# Expand_v1_02.net
KiCad netlist of a schematic drawn in EAGLE
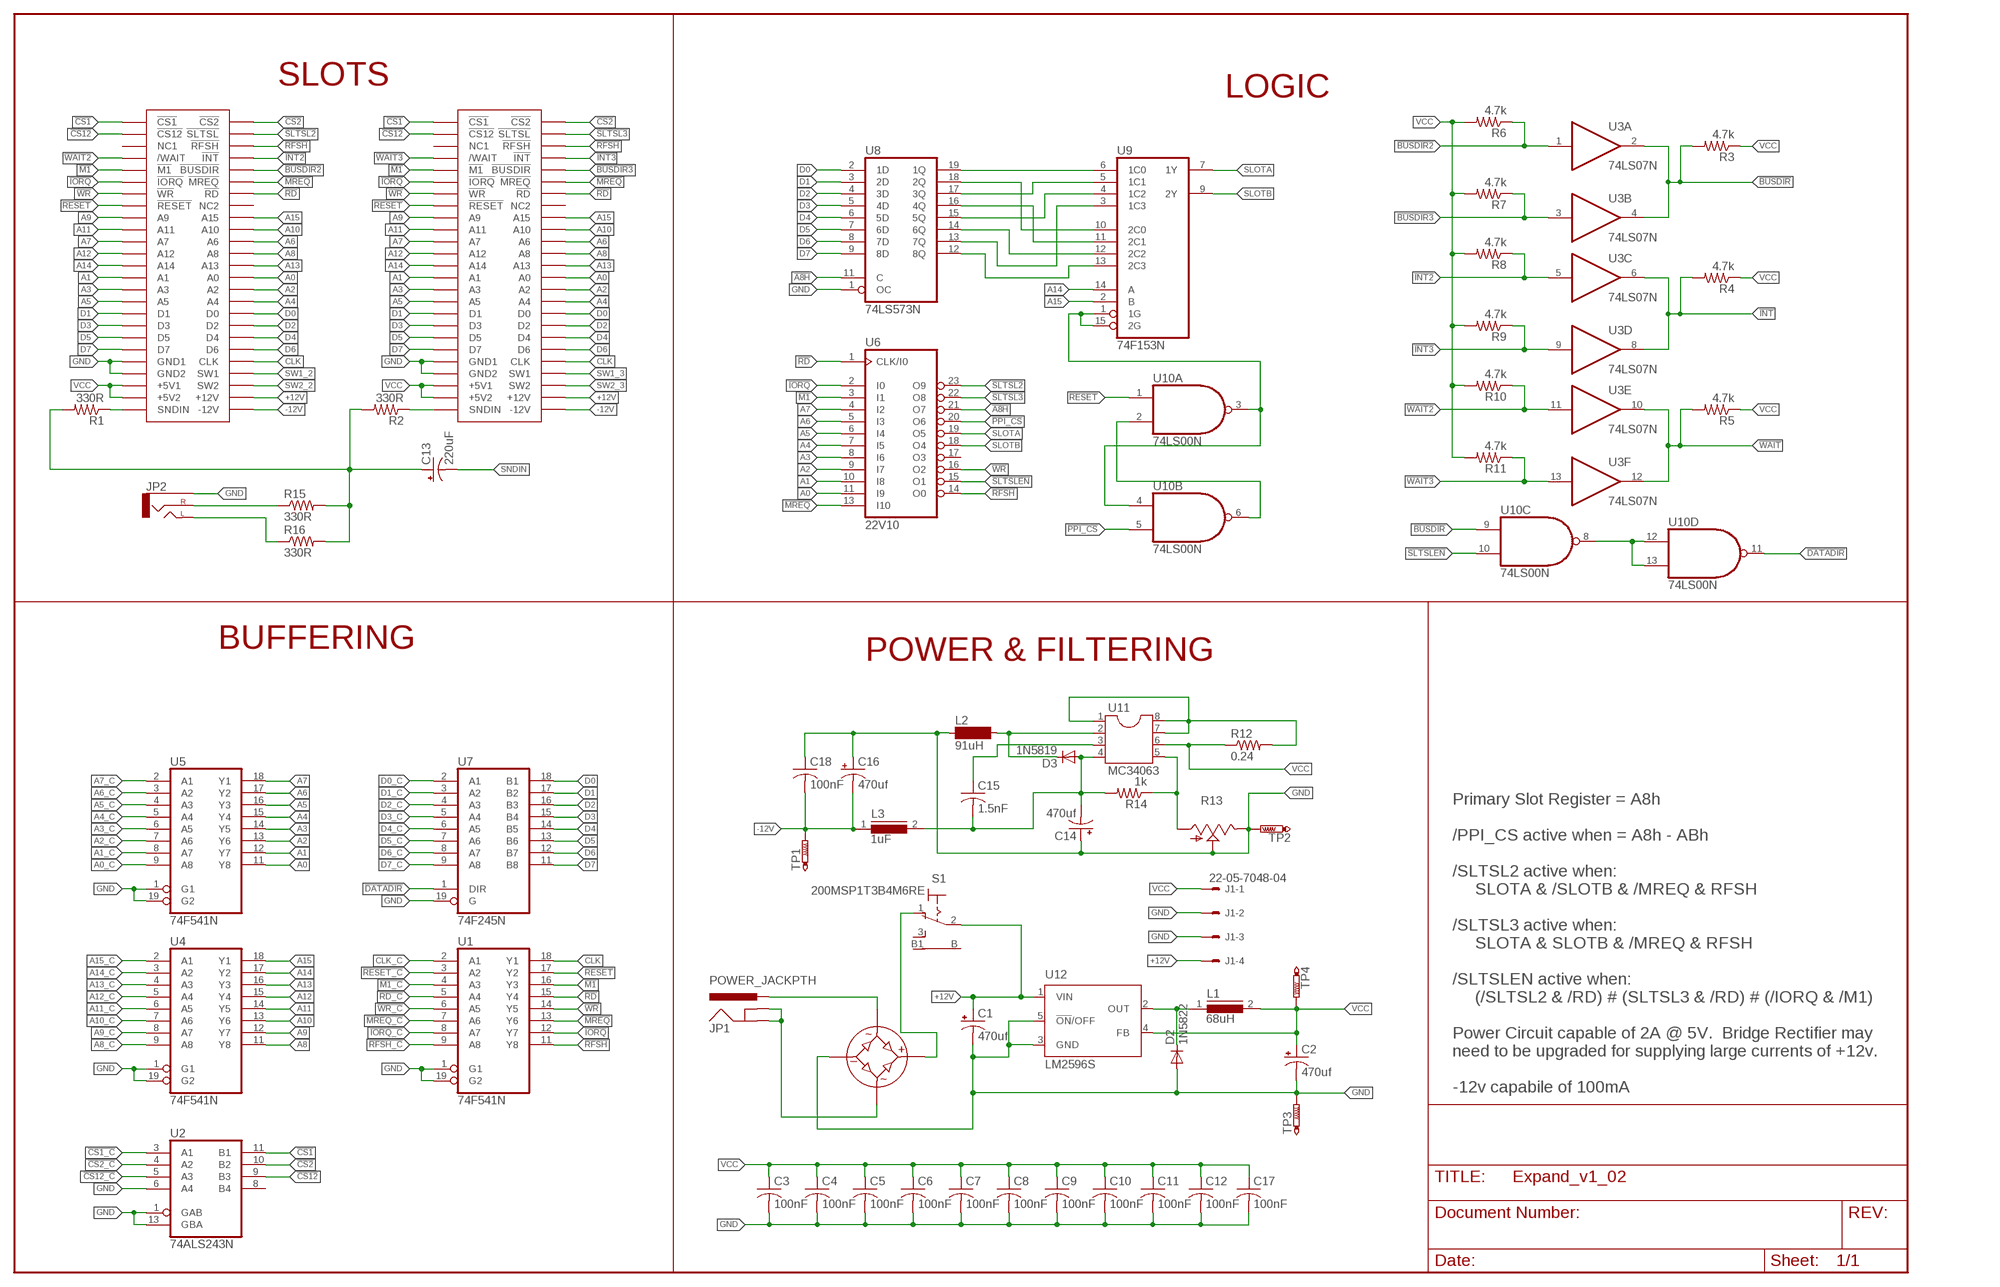
[diagram p0: schematic, sheet 1]

(export (version "E")
  (design (tool "Eeschema 10.0.6"))
  (components
    (comp (ref "C1")
      (value "470uf")
      (footprint "eagle-import:E5-10,5")
      (libsource (lib "eagle-import") (part "CPOL-USE5-10.5"))
    )
    (comp (ref "C2")
      (value "470uf")
      (footprint "eagle-import:E5-10,5")
      (libsource (lib "eagle-import") (part "CPOL-USE5-10.5"))
    )
    (comp (ref "C3")
      (value "100nF")
      (footprint "eagle-import:C050-030X075")
      (libsource (lib "eagle-import") (part "C-US050-030X075"))
    )
    (comp (ref "C4")
      (value "100nF")
      (footprint "eagle-import:C050-030X075")
      (libsource (lib "eagle-import") (part "C-US050-030X075"))
    )
    (comp (ref "C5")
      (value "100nF")
      (footprint "eagle-import:C050-030X075")
      (libsource (lib "eagle-import") (part "C-US050-030X075"))
    )
    (comp (ref "C6")
      (value "100nF")
      (footprint "eagle-import:C050-030X075")
      (libsource (lib "eagle-import") (part "C-US050-030X075"))
    )
    (comp (ref "C7")
      (value "100nF")
      (footprint "eagle-import:C050-030X075")
      (libsource (lib "eagle-import") (part "C-US050-030X075"))
    )
    (comp (ref "C8")
      (value "100nF")
      (footprint "eagle-import:C050-030X075")
      (libsource (lib "eagle-import") (part "C-US050-030X075"))
    )
    (comp (ref "C9")
      (value "100nF")
      (footprint "eagle-import:C050-030X075")
      (libsource (lib "eagle-import") (part "C-US050-030X075"))
    )
    (comp (ref "C10")
      (value "100nF")
      (footprint "eagle-import:C050-030X075")
      (libsource (lib "eagle-import") (part "C-US050-030X075"))
    )
    (comp (ref "C11")
      (value "100nF")
      (footprint "eagle-import:C050-030X075")
      (libsource (lib "eagle-import") (part "C-US050-030X075"))
    )
    (comp (ref "C12")
      (value "100nF")
      (footprint "eagle-import:C050-030X075")
      (libsource (lib "eagle-import") (part "C-US050-030X075"))
    )
    (comp (ref "C13")
      (value "220uF")
      (footprint "eagle-import:E2-4")
      (libsource (lib "eagle-import") (part "CPOL-USE2-4"))
    )
    (comp (ref "C14")
      (value "470uf")
      (footprint "eagle-import:E5-10,5")
      (libsource (lib "eagle-import") (part "CPOL-USE5-10.5"))
    )
    (comp (ref "C15")
      (value "1.5nF")
      (footprint "eagle-import:C050-030X075")
      (libsource (lib "eagle-import") (part "C-US050-030X075"))
    )
    (comp (ref "C16")
      (value "470uf")
      (footprint "eagle-import:E5-10,5")
      (libsource (lib "eagle-import") (part "CPOL-USE5-10.5"))
    )
    (comp (ref "C17")
      (value "100nF")
      (footprint "eagle-import:C050-030X075")
      (libsource (lib "eagle-import") (part "C-US050-030X075"))
    )
    (comp (ref "C18")
      (value "100nF")
      (footprint "eagle-import:C050-030X075")
      (libsource (lib "eagle-import") (part "C-US050-030X075"))
    )
    (comp (ref "CONN2")
      (value "MSX_CART_SLOT")
      (footprint "eagle-import:CART_SLOT")
      (libsource (lib "eagle-import") (part "MSX_CART_SLOT"))
    )
    (comp (ref "CONN3")
      (value "MSX_CART_SLOT")
      (footprint "eagle-import:CART_SLOT")
      (libsource (lib "eagle-import") (part "MSX_CART_SLOT"))
    )
    (comp (ref "D1")
      (value "2W10")
      (footprint "eagle-import:2W10")
      (libsource (lib "eagle-import") (part "2W10"))
    )
    (comp (ref "D2")
      (value "1N5822")
      (footprint "eagle-import:DO201-15")
      (libsource (lib "eagle-import") (part "1N5624"))
    )
    (comp (ref "D3")
      (value "1N5819")
      (footprint "eagle-import:DO15-12")
      (libsource (lib "eagle-import") (part "DIODE-DO15-12"))
    )
    (comp (ref "J1")
      (value "22-05-7048-04")
      (footprint "eagle-import:7395-04")
      (libsource (lib "eagle-import") (part "22-?-0405-7048"))
    )
    (comp (ref "JP1")
      (value "POWER_JACKPTH")
      (footprint "eagle-import:POWER_JACK_PTH")
      (libsource (lib "eagle-import") (part "POWER_JACKPTH"))
    )
    (comp (ref "JP2")
      (value "AUDIO-JACK1:1")
      (footprint "eagle-import:STEREOJACK2.5MM")
      (libsource (lib "eagle-import") (part "AUDIO-JACK1{colon}1"))
    )
    (comp (ref "L1")
      (value "68uH")
      (footprint "eagle-import:A26GFC")
      (libsource (lib "eagle-import") (part "A26GFC"))
    )
    (comp (ref "L2")
      (value "91uH")
      (footprint "eagle-import:BS11")
      (libsource (lib "eagle-import") (part "BS11"))
    )
    (comp (ref "L3")
      (value "1uF")
      (footprint "eagle-import:MCC10")
      (libsource (lib "eagle-import") (part "MCC10"))
    )
    (comp (ref "R1")
      (value "330R")
      (footprint "eagle-import:0207_7")
      (libsource (lib "eagle-import") (part "R-US_0207/7"))
    )
    (comp (ref "R2")
      (value "330R")
      (footprint "eagle-import:0207_7")
      (libsource (lib "eagle-import") (part "R-US_0207/7"))
    )
    (comp (ref "R3")
      (value "4.7k")
      (footprint "eagle-import:0207_7")
      (libsource (lib "eagle-import") (part "R-US_0207/7"))
    )
    (comp (ref "R4")
      (value "4.7k")
      (footprint "eagle-import:0207_7")
      (libsource (lib "eagle-import") (part "R-US_0207/7"))
    )
    (comp (ref "R5")
      (value "4.7k")
      (footprint "eagle-import:0207_7")
      (libsource (lib "eagle-import") (part "R-US_0207/7"))
    )
    (comp (ref "R6")
      (value "4.7k")
      (footprint "eagle-import:0207_7")
      (libsource (lib "eagle-import") (part "R-US_0207/7"))
    )
    (comp (ref "R7")
      (value "4.7k")
      (footprint "eagle-import:0207_7")
      (libsource (lib "eagle-import") (part "R-US_0207/7"))
    )
    (comp (ref "R8")
      (value "4.7k")
      (footprint "eagle-import:0207_7")
      (libsource (lib "eagle-import") (part "R-US_0207/7"))
    )
    (comp (ref "R9")
      (value "4.7k")
      (footprint "eagle-import:0207_7")
      (libsource (lib "eagle-import") (part "R-US_0207/7"))
    )
    (comp (ref "R10")
      (value "4.7k")
      (footprint "eagle-import:0207_7")
      (libsource (lib "eagle-import") (part "R-US_0207/7"))
    )
    (comp (ref "R11")
      (value "4.7k")
      (footprint "eagle-import:0207_7")
      (libsource (lib "eagle-import") (part "R-US_0207/7"))
    )
    (comp (ref "R12")
      (value "0.24")
      (footprint "eagle-import:0207_10")
      (libsource (lib "eagle-import") (part "R-US_0207/10"))
    )
    (comp (ref "R13")
      (value "TRIM_US-RJ9W")
      (footprint "eagle-import:RJ9W")
      (libsource (lib "eagle-import") (part "TRIM_US-RJ9W"))
    )
    (comp (ref "R14")
      (value "1k")
      (footprint "eagle-import:0207_7")
      (libsource (lib "eagle-import") (part "R-US_0207/7"))
    )
    (comp (ref "R15")
      (value "330R")
      (footprint "eagle-import:0207_7")
      (libsource (lib "eagle-import") (part "R-US_0207/7"))
    )
    (comp (ref "R16")
      (value "330R")
      (footprint "eagle-import:0207_7")
      (libsource (lib "eagle-import") (part "R-US_0207/7"))
    )
    (comp (ref "S1")
      (value "200MSP1T3B4M6RE")
      (footprint "eagle-import:9070-1W")
      (libsource (lib "eagle-import") (part "9070-1W"))
    )
    (comp (ref "TP1")
      (value "PTR1B2,54")
      (footprint "eagle-import:B2,54")
      (libsource (lib "eagle-import") (part "PTR1B2,54"))
    )
    (comp (ref "TP2")
      (value "PTR1B2,54")
      (footprint "eagle-import:B2,54")
      (libsource (lib "eagle-import") (part "PTR1B2,54"))
    )
    (comp (ref "TP3")
      (value "PTR1B2,54")
      (footprint "eagle-import:B2,54")
      (libsource (lib "eagle-import") (part "PTR1B2,54"))
    )
    (comp (ref "TP4")
      (value "PTR1B2,54")
      (footprint "eagle-import:B2,54")
      (libsource (lib "eagle-import") (part "PTR1B2,54"))
    )
    (comp (ref "U1")
      (value "74F541N")
      (footprint "eagle-import:DIL20")
      (libsource (lib "eagle-import") (part "74541NLS"))
    )
    (comp (ref "U2")
      (value "74ALS243N")
      (footprint "eagle-import:DIL14")
      (libsource (lib "eagle-import") (part "74243NLS"))
    )
    (comp (ref "U3")
      (value "74LS07N")
      (footprint "eagle-import:DIL14")
      (libsource (lib "eagle-import") (part "7407N"))
    )
    (comp (ref "U4")
      (value "74F541N")
      (footprint "eagle-import:DIL20")
      (libsource (lib "eagle-import") (part "74541NLS"))
    )
    (comp (ref "U5")
      (value "74F541N")
      (footprint "eagle-import:DIL20")
      (libsource (lib "eagle-import") (part "74541NLS"))
    )
    (comp (ref "U6")
      (value "22V10")
      (footprint "eagle-import:DIL24-3")
      (fields (field (name "MPN") "GAL22V10D-7LPN"))
      (libsource (lib "eagle-import") (part "22V10"))
    )
    (comp (ref "U7")
      (value "74F245N")
      (footprint "eagle-import:DIL20")
      (libsource (lib "eagle-import") (part "74245NLS"))
    )
    (comp (ref "U8")
      (value "74LS573N")
      (footprint "eagle-import:DIL20")
      (libsource (lib "eagle-import") (part "74573NAS"))
    )
    (comp (ref "U9")
      (value "74F153N")
      (footprint "eagle-import:DIL16")
      (libsource (lib "eagle-import") (part "74153NS"))
    )
    (comp (ref "U10")
      (value "74LS00N")
      (footprint "eagle-import:DIL14")
      (libsource (lib "eagle-import") (part "7400N"))
    )
    (comp (ref "U11")
      (value "MC34063")
      (footprint "eagle-import:DIL08")
      (libsource (lib "eagle-import") (part "DIL8"))
    )
    (comp (ref "U12")
      (value "LM2596S")
      (footprint "eagle-import:TO263-5")
      (fields (field (name "MF") "NATIONAL SEMICONDUCTOR") (field (name "MPN") "LM2596S-ADJ/NOPB"))
      (libsource (lib "eagle-import") (part "LM2596S"))
    )
  )
  (nets
    (net (code "1") (name "+12V") (class "Default")
      (node (ref "C1") (pin "+") (pinfunction "+_+") (pintype "passive"))
      (node (ref "CONN2") (pin "P$48") (pinfunction "+12V_P$48") (pintype "bidirectional"))
      (node (ref "CONN3") (pin "P$48") (pinfunction "+12V_P$48") (pintype "bidirectional"))
      (node (ref "J1") (pin "4") (pinfunction "S_4") (pintype "passive"))
      (node (ref "S1") (pin "2") (pinfunction "P_2") (pintype "passive"))
      (node (ref "U12") (pin "1") (pinfunction "VIN_1") (pintype "input"))
    )
    (net (code "2") (name "-12V") (class "Default")
      (node (ref "C16") (pin "-") (pinfunction "-_-") (pintype "passive"))
      (node (ref "C18") (pin "2") (pinfunction "2_2") (pintype "passive"))
      (node (ref "CONN2") (pin "P$50") (pinfunction "-12V_P$50") (pintype "bidirectional"))
      (node (ref "CONN3") (pin "P$50") (pinfunction "-12V_P$50") (pintype "bidirectional"))
      (node (ref "L3") (pin "1") (pinfunction "1_1") (pintype "passive"))
      (node (ref "TP1") (pin "TP") (pinfunction "TP_TP") (pintype "input"))
    )
    (net (code "3") (name "/~{A8H}") (class "Default")
      (node (ref "U6") (pin "21") (pinfunction "O7_21") (pintype "bidirectional"))
      (node (ref "U8") (pin "11") (pinfunction "C_11") (pintype "input"))
    )
    (net (code "4") (name "/~{BUSDIR2}") (class "Default")
      (node (ref "CONN2") (pin "P$10") (pinfunction "~{BUSDIR}_P$10") (pintype "bidirectional"))
      (node (ref "R6") (pin "1") (pinfunction "1_1") (pintype "passive"))
      (node (ref "U3") (pin "1") (pinfunction "I_1") (pintype "input"))
    )
    (net (code "5") (name "/~{BUSDIR3}") (class "Default")
      (node (ref "CONN3") (pin "P$10") (pinfunction "~{BUSDIR}_P$10") (pintype "bidirectional"))
      (node (ref "R7") (pin "1") (pinfunction "1_1") (pintype "passive"))
      (node (ref "U3") (pin "3") (pinfunction "I_3") (pintype "input"))
    )
    (net (code "6") (name "/~{BUSDIR}") (class "Default")
      (node (ref "R3") (pin "2") (pinfunction "2_2") (pintype "passive"))
      (node (ref "U10") (pin "9") (pinfunction "I0_9") (pintype "input"))
      (node (ref "U3") (pin "2") (pinfunction "O_2") (pintype "open_collector"))
      (node (ref "U3") (pin "4") (pinfunction "O_4") (pintype "open_collector"))
    )
    (net (code "7") (name "/~{CS1_C}") (class "Default")
      (node (ref "U2") (pin "3") (pinfunction "A1_3") (pintype "bidirectional"))
    )
    (net (code "8") (name "/~{CS1}") (class "Default")
      (node (ref "CONN2") (pin "P$1") (pinfunction "~{CS1}_P$1") (pintype "bidirectional"))
      (node (ref "CONN3") (pin "P$1") (pinfunction "~{CS1}_P$1") (pintype "bidirectional"))
      (node (ref "U2") (pin "11") (pinfunction "B1_11") (pintype "bidirectional"))
    )
    (net (code "9") (name "/~{CS2_C}") (class "Default")
      (node (ref "U2") (pin "4") (pinfunction "A2_4") (pintype "bidirectional"))
    )
    (net (code "10") (name "/~{CS2}") (class "Default")
      (node (ref "CONN2") (pin "P$2") (pinfunction "~{CS2}_P$2") (pintype "bidirectional"))
      (node (ref "CONN3") (pin "P$2") (pinfunction "~{CS2}_P$2") (pintype "bidirectional"))
      (node (ref "U2") (pin "10") (pinfunction "B2_10") (pintype "bidirectional"))
    )
    (net (code "11") (name "/~{CS12_C}") (class "Default")
      (node (ref "U2") (pin "5") (pinfunction "A3_5") (pintype "bidirectional"))
    )
    (net (code "12") (name "/~{CS12}") (class "Default")
      (node (ref "CONN2") (pin "P$3") (pinfunction "~{CS12}_P$3") (pintype "bidirectional"))
      (node (ref "CONN3") (pin "P$3") (pinfunction "~{CS12}_P$3") (pintype "bidirectional"))
      (node (ref "U2") (pin "9") (pinfunction "B3_9") (pintype "bidirectional"))
    )
    (net (code "13") (name "/~{DATADIR}") (class "Default")
      (node (ref "U10") (pin "11") (pinfunction "O_11") (pintype "output"))
      (node (ref "U7") (pin "1") (pinfunction "DIR_1") (pintype "input"))
    )
    (net (code "14") (name "/~{INT2}") (class "Default")
      (node (ref "CONN2") (pin "P$8") (pinfunction "~{INT}_P$8") (pintype "bidirectional"))
      (node (ref "R8") (pin "1") (pinfunction "1_1") (pintype "passive"))
      (node (ref "U3") (pin "5") (pinfunction "I_5") (pintype "input"))
    )
    (net (code "15") (name "/~{INT3}") (class "Default")
      (node (ref "CONN3") (pin "P$8") (pinfunction "~{INT}_P$8") (pintype "bidirectional"))
      (node (ref "R9") (pin "1") (pinfunction "1_1") (pintype "passive"))
      (node (ref "U3") (pin "9") (pinfunction "I_9") (pintype "input"))
    )
    (net (code "16") (name "/~{INT}") (class "Default")
      (node (ref "R4") (pin "2") (pinfunction "2_2") (pintype "passive"))
      (node (ref "U3") (pin "6") (pinfunction "O_6") (pintype "open_collector"))
      (node (ref "U3") (pin "8") (pinfunction "O_8") (pintype "open_collector"))
    )
    (net (code "17") (name "/~{IORQ_C}") (class "Default")
      (node (ref "U1") (pin "8") (pinfunction "A7_8") (pintype "input"))
    )
    (net (code "18") (name "/~{IORQ}") (class "Default")
      (node (ref "CONN2") (pin "P$11") (pinfunction "~{IORQ}_P$11") (pintype "bidirectional"))
      (node (ref "CONN3") (pin "P$11") (pinfunction "~{IORQ}_P$11") (pintype "bidirectional"))
      (node (ref "U1") (pin "12") (pinfunction "Y7_12") (pintype "tri_state"))
      (node (ref "U6") (pin "2") (pinfunction "I0_2") (pintype "input"))
    )
    (net (code "19") (name "/~{M1_C}") (class "Default")
      (node (ref "U1") (pin "4") (pinfunction "A3_4") (pintype "input"))
    )
    (net (code "20") (name "/~{M1}") (class "Default")
      (node (ref "CONN2") (pin "P$9") (pinfunction "~{M1}_P$9") (pintype "bidirectional"))
      (node (ref "CONN3") (pin "P$9") (pinfunction "~{M1}_P$9") (pintype "bidirectional"))
      (node (ref "U1") (pin "16") (pinfunction "Y3_16") (pintype "tri_state"))
      (node (ref "U6") (pin "3") (pinfunction "I1_3") (pintype "input"))
    )
    (net (code "21") (name "/~{MREQ_C}") (class "Default")
      (node (ref "U1") (pin "7") (pinfunction "A6_7") (pintype "input"))
    )
    (net (code "22") (name "/~{MREQ}") (class "Default")
      (node (ref "CONN2") (pin "P$12") (pinfunction "~{MREQ}_P$12") (pintype "bidirectional"))
      (node (ref "CONN3") (pin "P$12") (pinfunction "~{MREQ}_P$12") (pintype "bidirectional"))
      (node (ref "U1") (pin "13") (pinfunction "Y6_13") (pintype "tri_state"))
      (node (ref "U6") (pin "13") (pinfunction "I10_13") (pintype "input"))
    )
    (net (code "23") (name "/~{PPI_CS}") (class "Default")
      (node (ref "U10") (pin "5") (pinfunction "I1_5") (pintype "input"))
      (node (ref "U6") (pin "20") (pinfunction "O6_20") (pintype "bidirectional"))
    )
    (net (code "24") (name "/~{RD_C}") (class "Default")
      (node (ref "U1") (pin "5") (pinfunction "A4_5") (pintype "input"))
    )
    (net (code "25") (name "/~{RD}") (class "Default")
      (node (ref "CONN2") (pin "P$14") (pinfunction "~{RD}_P$14") (pintype "bidirectional"))
      (node (ref "CONN3") (pin "P$14") (pinfunction "~{RD}_P$14") (pintype "bidirectional"))
      (node (ref "U1") (pin "15") (pinfunction "Y4_15") (pintype "tri_state"))
      (node (ref "U6") (pin "1") (pinfunction "CLK/I0_1") (pintype "input"))
    )
    (net (code "26") (name "/~{RESET_C}") (class "Default")
      (node (ref "U1") (pin "3") (pinfunction "A2_3") (pintype "input"))
    )
    (net (code "27") (name "/~{RESET}") (class "Default")
      (node (ref "CONN2") (pin "P$15") (pinfunction "~{RESET}_P$15") (pintype "bidirectional"))
      (node (ref "CONN3") (pin "P$15") (pinfunction "~{RESET}_P$15") (pintype "bidirectional"))
      (node (ref "U1") (pin "17") (pinfunction "Y2_17") (pintype "tri_state"))
      (node (ref "U10") (pin "1") (pinfunction "I0_1") (pintype "input"))
    )
    (net (code "28") (name "/~{RFSH_C}") (class "Default")
      (node (ref "U1") (pin "9") (pinfunction "A8_9") (pintype "input"))
    )
    (net (code "29") (name "/~{RFSH}") (class "Default")
      (node (ref "CONN2") (pin "P$6") (pinfunction "~{RFSH}_P$6") (pintype "bidirectional"))
      (node (ref "CONN3") (pin "P$6") (pinfunction "~{RFSH}_P$6") (pintype "bidirectional"))
      (node (ref "U1") (pin "11") (pinfunction "Y8_11") (pintype "tri_state"))
      (node (ref "U6") (pin "14") (pinfunction "O0_14") (pintype "bidirectional"))
    )
    (net (code "30") (name "/~{SLTSL2}") (class "Default")
      (node (ref "CONN2") (pin "P$4") (pinfunction "~{SLTSL}_P$4") (pintype "bidirectional"))
      (node (ref "U6") (pin "23") (pinfunction "O9_23") (pintype "bidirectional"))
    )
    (net (code "31") (name "/~{SLTSL3}") (class "Default")
      (node (ref "CONN3") (pin "P$4") (pinfunction "~{SLTSL}_P$4") (pintype "bidirectional"))
      (node (ref "U6") (pin "22") (pinfunction "O8_22") (pintype "bidirectional"))
    )
    (net (code "32") (name "/~{SLTSLEN}") (class "Default")
      (node (ref "U10") (pin "10") (pinfunction "I1_10") (pintype "input"))
      (node (ref "U6") (pin "15") (pinfunction "O1_15") (pintype "bidirectional"))
    )
    (net (code "33") (name "/~{WAIT2}") (class "Default")
      (node (ref "CONN2") (pin "P$7") (pinfunction "/WAIT_P$7") (pintype "bidirectional"))
      (node (ref "R10") (pin "1") (pinfunction "1_1") (pintype "passive"))
      (node (ref "U3") (pin "11") (pinfunction "I_11") (pintype "input"))
    )
    (net (code "34") (name "/~{WAIT3}") (class "Default")
      (node (ref "CONN3") (pin "P$7") (pinfunction "/WAIT_P$7") (pintype "bidirectional"))
      (node (ref "R11") (pin "1") (pinfunction "1_1") (pintype "passive"))
      (node (ref "U3") (pin "13") (pinfunction "I_13") (pintype "input"))
    )
    (net (code "35") (name "/~{WAIT}") (class "Default")
      (node (ref "R5") (pin "2") (pinfunction "2_2") (pintype "passive"))
      (node (ref "U3") (pin "10") (pinfunction "O_10") (pintype "open_collector"))
      (node (ref "U3") (pin "12") (pinfunction "O_12") (pintype "open_collector"))
    )
    (net (code "36") (name "/~{WR_C}") (class "Default")
      (node (ref "U1") (pin "6") (pinfunction "A5_6") (pintype "input"))
    )
    (net (code "37") (name "/~{WR}") (class "Default")
      (node (ref "CONN2") (pin "P$13") (pinfunction "~{WR}_P$13") (pintype "bidirectional"))
      (node (ref "CONN3") (pin "P$13") (pinfunction "~{WR}_P$13") (pintype "bidirectional"))
      (node (ref "U1") (pin "14") (pinfunction "Y5_14") (pintype "tri_state"))
      (node (ref "U6") (pin "16") (pinfunction "O2_16") (pintype "bidirectional"))
    )
    (net (code "38") (name "A0") (class "Default")
      (node (ref "CONN2") (pin "P$28") (pinfunction "A0_P$28") (pintype "bidirectional"))
      (node (ref "CONN3") (pin "P$28") (pinfunction "A0_P$28") (pintype "bidirectional"))
      (node (ref "U5") (pin "11") (pinfunction "Y8_11") (pintype "tri_state"))
      (node (ref "U6") (pin "11") (pinfunction "I9_11") (pintype "input"))
    )
    (net (code "39") (name "A0_C") (class "Default")
      (node (ref "U5") (pin "9") (pinfunction "A8_9") (pintype "input"))
    )
    (net (code "40") (name "A1") (class "Default")
      (node (ref "CONN2") (pin "P$27") (pinfunction "A1_P$27") (pintype "bidirectional"))
      (node (ref "CONN3") (pin "P$27") (pinfunction "A1_P$27") (pintype "bidirectional"))
      (node (ref "U5") (pin "12") (pinfunction "Y7_12") (pintype "tri_state"))
      (node (ref "U6") (pin "10") (pinfunction "I8_10") (pintype "input"))
    )
    (net (code "41") (name "A1_C") (class "Default")
      (node (ref "U5") (pin "8") (pinfunction "A7_8") (pintype "input"))
    )
    (net (code "42") (name "A2") (class "Default")
      (node (ref "CONN2") (pin "P$30") (pinfunction "A2_P$30") (pintype "bidirectional"))
      (node (ref "CONN3") (pin "P$30") (pinfunction "A2_P$30") (pintype "bidirectional"))
      (node (ref "U5") (pin "13") (pinfunction "Y6_13") (pintype "tri_state"))
      (node (ref "U6") (pin "9") (pinfunction "I7_9") (pintype "input"))
    )
    (net (code "43") (name "A2_C") (class "Default")
      (node (ref "U5") (pin "7") (pinfunction "A6_7") (pintype "input"))
    )
    (net (code "44") (name "A3") (class "Default")
      (node (ref "CONN2") (pin "P$29") (pinfunction "A3_P$29") (pintype "bidirectional"))
      (node (ref "CONN3") (pin "P$29") (pinfunction "A3_P$29") (pintype "bidirectional"))
      (node (ref "U5") (pin "14") (pinfunction "Y5_14") (pintype "tri_state"))
      (node (ref "U6") (pin "8") (pinfunction "I6_8") (pintype "input"))
    )
    (net (code "45") (name "A3_C") (class "Default")
      (node (ref "U5") (pin "6") (pinfunction "A5_6") (pintype "input"))
    )
    (net (code "46") (name "A4") (class "Default")
      (node (ref "CONN2") (pin "P$32") (pinfunction "A4_P$32") (pintype "bidirectional"))
      (node (ref "CONN3") (pin "P$32") (pinfunction "A4_P$32") (pintype "bidirectional"))
      (node (ref "U5") (pin "15") (pinfunction "Y4_15") (pintype "tri_state"))
      (node (ref "U6") (pin "7") (pinfunction "I5_7") (pintype "input"))
    )
    (net (code "47") (name "A4_C") (class "Default")
      (node (ref "U5") (pin "5") (pinfunction "A4_5") (pintype "input"))
    )
    (net (code "48") (name "A5") (class "Default")
      (node (ref "CONN2") (pin "P$31") (pinfunction "A5_P$31") (pintype "bidirectional"))
      (node (ref "CONN3") (pin "P$31") (pinfunction "A5_P$31") (pintype "bidirectional"))
      (node (ref "U5") (pin "16") (pinfunction "Y3_16") (pintype "tri_state"))
      (node (ref "U6") (pin "6") (pinfunction "I4_6") (pintype "input"))
    )
    (net (code "49") (name "A5_C") (class "Default")
      (node (ref "U5") (pin "4") (pinfunction "A3_4") (pintype "input"))
    )
    (net (code "50") (name "A6") (class "Default")
      (node (ref "CONN2") (pin "P$22") (pinfunction "A6_P$22") (pintype "bidirectional"))
      (node (ref "CONN3") (pin "P$22") (pinfunction "A6_P$22") (pintype "bidirectional"))
      (node (ref "U5") (pin "17") (pinfunction "Y2_17") (pintype "tri_state"))
      (node (ref "U6") (pin "5") (pinfunction "I3_5") (pintype "input"))
    )
    (net (code "51") (name "A6_C") (class "Default")
      (node (ref "U5") (pin "3") (pinfunction "A2_3") (pintype "input"))
    )
    (net (code "52") (name "A7") (class "Default")
      (node (ref "CONN2") (pin "P$21") (pinfunction "A7_P$21") (pintype "bidirectional"))
      (node (ref "CONN3") (pin "P$21") (pinfunction "A7_P$21") (pintype "bidirectional"))
      (node (ref "U5") (pin "18") (pinfunction "Y1_18") (pintype "tri_state"))
      (node (ref "U6") (pin "4") (pinfunction "I2_4") (pintype "input"))
    )
    (net (code "53") (name "A7_C") (class "Default")
      (node (ref "U5") (pin "2") (pinfunction "A1_2") (pintype "input"))
    )
    (net (code "54") (name "A8") (class "Default")
      (node (ref "CONN2") (pin "P$24") (pinfunction "A8_P$24") (pintype "bidirectional"))
      (node (ref "CONN3") (pin "P$24") (pinfunction "A8_P$24") (pintype "bidirectional"))
      (node (ref "U4") (pin "11") (pinfunction "Y8_11") (pintype "tri_state"))
    )
    (net (code "55") (name "A8_C") (class "Default")
      (node (ref "U4") (pin "9") (pinfunction "A8_9") (pintype "input"))
    )
    (net (code "56") (name "A9") (class "Default")
      (node (ref "CONN2") (pin "P$17") (pinfunction "A9_P$17") (pintype "bidirectional"))
      (node (ref "CONN3") (pin "P$17") (pinfunction "A9_P$17") (pintype "bidirectional"))
      (node (ref "U4") (pin "12") (pinfunction "Y7_12") (pintype "tri_state"))
    )
    (net (code "57") (name "A9_C") (class "Default")
      (node (ref "U4") (pin "8") (pinfunction "A7_8") (pintype "input"))
    )
    (net (code "58") (name "A10") (class "Default")
      (node (ref "CONN2") (pin "P$20") (pinfunction "A10_P$20") (pintype "bidirectional"))
      (node (ref "CONN3") (pin "P$20") (pinfunction "A10_P$20") (pintype "bidirectional"))
      (node (ref "U4") (pin "13") (pinfunction "Y6_13") (pintype "tri_state"))
    )
    (net (code "59") (name "A10_C") (class "Default")
      (node (ref "U4") (pin "7") (pinfunction "A6_7") (pintype "input"))
    )
    (net (code "60") (name "A11") (class "Default")
      (node (ref "CONN2") (pin "P$19") (pinfunction "A11_P$19") (pintype "bidirectional"))
      (node (ref "CONN3") (pin "P$19") (pinfunction "A11_P$19") (pintype "bidirectional"))
      (node (ref "U4") (pin "14") (pinfunction "Y5_14") (pintype "tri_state"))
    )
    (net (code "61") (name "A11_C") (class "Default")
      (node (ref "U4") (pin "6") (pinfunction "A5_6") (pintype "input"))
    )
    (net (code "62") (name "A12") (class "Default")
      (node (ref "CONN2") (pin "P$23") (pinfunction "A12_P$23") (pintype "bidirectional"))
      (node (ref "CONN3") (pin "P$23") (pinfunction "A12_P$23") (pintype "bidirectional"))
      (node (ref "U4") (pin "15") (pinfunction "Y4_15") (pintype "tri_state"))
    )
    (net (code "63") (name "A12_C") (class "Default")
      (node (ref "U4") (pin "5") (pinfunction "A4_5") (pintype "input"))
    )
    (net (code "64") (name "A13") (class "Default")
      (node (ref "CONN2") (pin "P$26") (pinfunction "A13_P$26") (pintype "bidirectional"))
      (node (ref "CONN3") (pin "P$26") (pinfunction "A13_P$26") (pintype "bidirectional"))
      (node (ref "U4") (pin "16") (pinfunction "Y3_16") (pintype "tri_state"))
    )
    (net (code "65") (name "A13_C") (class "Default")
      (node (ref "U4") (pin "4") (pinfunction "A3_4") (pintype "input"))
    )
    (net (code "66") (name "A14") (class "Default")
      (node (ref "CONN2") (pin "P$25") (pinfunction "A14_P$25") (pintype "bidirectional"))
      (node (ref "CONN3") (pin "P$25") (pinfunction "A14_P$25") (pintype "bidirectional"))
      (node (ref "U4") (pin "17") (pinfunction "Y2_17") (pintype "tri_state"))
      (node (ref "U9") (pin "14") (pinfunction "A_14") (pintype "input"))
    )
    (net (code "67") (name "A14_C") (class "Default")
      (node (ref "U4") (pin "3") (pinfunction "A2_3") (pintype "input"))
    )
    (net (code "68") (name "A15") (class "Default")
      (node (ref "CONN2") (pin "P$18") (pinfunction "A15_P$18") (pintype "bidirectional"))
      (node (ref "CONN3") (pin "P$18") (pinfunction "A15_P$18") (pintype "bidirectional"))
      (node (ref "U4") (pin "18") (pinfunction "Y1_18") (pintype "tri_state"))
      (node (ref "U9") (pin "2") (pinfunction "B_2") (pintype "input"))
    )
    (net (code "69") (name "A15_C") (class "Default")
      (node (ref "U4") (pin "2") (pinfunction "A1_2") (pintype "input"))
    )
    (net (code "70") (name "CLK") (class "Default")
      (node (ref "CONN2") (pin "P$42") (pinfunction "CLK_P$42") (pintype "bidirectional"))
      (node (ref "CONN3") (pin "P$42") (pinfunction "CLK_P$42") (pintype "bidirectional"))
      (node (ref "U1") (pin "18") (pinfunction "Y1_18") (pintype "tri_state"))
    )
    (net (code "71") (name "CLK_C") (class "Default")
      (node (ref "U1") (pin "2") (pinfunction "A1_2") (pintype "input"))
    )
    (net (code "72") (name "D0") (class "Default")
      (node (ref "CONN2") (pin "P$34") (pinfunction "D0_P$34") (pintype "bidirectional"))
      (node (ref "CONN3") (pin "P$34") (pinfunction "D0_P$34") (pintype "bidirectional"))
      (node (ref "U7") (pin "18") (pinfunction "B1_18") (pintype "bidirectional"))
      (node (ref "U8") (pin "2") (pinfunction "1D_2") (pintype "input"))
    )
    (net (code "73") (name "D0_C") (class "Default")
      (node (ref "U7") (pin "2") (pinfunction "A1_2") (pintype "bidirectional"))
    )
    (net (code "74") (name "D1") (class "Default")
      (node (ref "CONN2") (pin "P$33") (pinfunction "D1_P$33") (pintype "bidirectional"))
      (node (ref "CONN3") (pin "P$33") (pinfunction "D1_P$33") (pintype "bidirectional"))
      (node (ref "U7") (pin "17") (pinfunction "B2_17") (pintype "bidirectional"))
      (node (ref "U8") (pin "3") (pinfunction "2D_3") (pintype "input"))
    )
    (net (code "75") (name "D1_C") (class "Default")
      (node (ref "U7") (pin "3") (pinfunction "A2_3") (pintype "bidirectional"))
    )
    (net (code "76") (name "D2") (class "Default")
      (node (ref "CONN2") (pin "P$36") (pinfunction "D2_P$36") (pintype "bidirectional"))
      (node (ref "CONN3") (pin "P$36") (pinfunction "D2_P$36") (pintype "bidirectional"))
      (node (ref "U7") (pin "16") (pinfunction "B3_16") (pintype "bidirectional"))
      (node (ref "U8") (pin "4") (pinfunction "3D_4") (pintype "input"))
    )
    (net (code "77") (name "D2_C") (class "Default")
      (node (ref "U7") (pin "4") (pinfunction "A3_4") (pintype "bidirectional"))
    )
    (net (code "78") (name "D3") (class "Default")
      (node (ref "CONN2") (pin "P$35") (pinfunction "D3_P$35") (pintype "bidirectional"))
      (node (ref "CONN3") (pin "P$35") (pinfunction "D3_P$35") (pintype "bidirectional"))
      (node (ref "U7") (pin "15") (pinfunction "B4_15") (pintype "bidirectional"))
      (node (ref "U8") (pin "5") (pinfunction "4D_5") (pintype "input"))
    )
    (net (code "79") (name "D3_C") (class "Default")
      (node (ref "U7") (pin "5") (pinfunction "A4_5") (pintype "bidirectional"))
    )
    (net (code "80") (name "D4") (class "Default")
      (node (ref "CONN2") (pin "P$38") (pinfunction "D4_P$38") (pintype "bidirectional"))
      (node (ref "CONN3") (pin "P$38") (pinfunction "D4_P$38") (pintype "bidirectional"))
      (node (ref "U7") (pin "14") (pinfunction "B5_14") (pintype "bidirectional"))
      (node (ref "U8") (pin "6") (pinfunction "5D_6") (pintype "input"))
    )
    (net (code "81") (name "D4_C") (class "Default")
      (node (ref "U7") (pin "6") (pinfunction "A5_6") (pintype "bidirectional"))
    )
    (net (code "82") (name "D5") (class "Default")
      (node (ref "CONN2") (pin "P$37") (pinfunction "D5_P$37") (pintype "bidirectional"))
      (node (ref "CONN3") (pin "P$37") (pinfunction "D5_P$37") (pintype "bidirectional"))
      (node (ref "U7") (pin "13") (pinfunction "B6_13") (pintype "bidirectional"))
      (node (ref "U8") (pin "7") (pinfunction "6D_7") (pintype "input"))
    )
    (net (code "83") (name "D5_C") (class "Default")
      (node (ref "U7") (pin "7") (pinfunction "A6_7") (pintype "bidirectional"))
    )
    (net (code "84") (name "D6") (class "Default")
      (node (ref "CONN2") (pin "P$40") (pinfunction "D6_P$40") (pintype "bidirectional"))
      (node (ref "CONN3") (pin "P$40") (pinfunction "D6_P$40") (pintype "bidirectional"))
      (node (ref "U7") (pin "12") (pinfunction "B7_12") (pintype "bidirectional"))
      (node (ref "U8") (pin "8") (pinfunction "7D_8") (pintype "input"))
    )
    (net (code "85") (name "D6_C") (class "Default")
      (node (ref "U7") (pin "8") (pinfunction "A7_8") (pintype "bidirectional"))
    )
    (net (code "86") (name "D7") (class "Default")
      (node (ref "CONN2") (pin "P$39") (pinfunction "D7_P$39") (pintype "bidirectional"))
      (node (ref "CONN3") (pin "P$39") (pinfunction "D7_P$39") (pintype "bidirectional"))
      (node (ref "U7") (pin "11") (pinfunction "B8_11") (pintype "bidirectional"))
      (node (ref "U8") (pin "9") (pinfunction "8D_9") (pintype "input"))
    )
    (net (code "87") (name "D7_C") (class "Default")
      (node (ref "U7") (pin "9") (pinfunction "A8_9") (pintype "bidirectional"))
    )
    (net (code "88") (name "GND") (class "Default")
      (node (ref "C1") (pin "-") (pinfunction "-_-") (pintype "passive"))
      (node (ref "C10") (pin "2") (pinfunction "2_2") (pintype "passive"))
      (node (ref "C11") (pin "2") (pinfunction "2_2") (pintype "passive"))
      (node (ref "C12") (pin "2") (pinfunction "2_2") (pintype "passive"))
      (node (ref "C14") (pin "+") (pinfunction "+_+") (pintype "passive"))
      (node (ref "C16") (pin "+") (pinfunction "+_+") (pintype "passive"))
      (node (ref "C17") (pin "2") (pinfunction "2_2") (pintype "passive"))
      (node (ref "C18") (pin "1") (pinfunction "1_1") (pintype "passive"))
      (node (ref "C2") (pin "-") (pinfunction "-_-") (pintype "passive"))
      (node (ref "C3") (pin "2") (pinfunction "2_2") (pintype "passive"))
      (node (ref "C4") (pin "2") (pinfunction "2_2") (pintype "passive"))
      (node (ref "C5") (pin "2") (pinfunction "2_2") (pintype "passive"))
      (node (ref "C6") (pin "2") (pinfunction "2_2") (pintype "passive"))
      (node (ref "C7") (pin "2") (pinfunction "2_2") (pintype "passive"))
      (node (ref "C8") (pin "2") (pinfunction "2_2") (pintype "passive"))
      (node (ref "C9") (pin "2") (pinfunction "2_2") (pintype "passive"))
      (node (ref "CONN2") (pin "P$41") (pinfunction "GND1_P$41") (pintype "bidirectional"))
      (node (ref "CONN2") (pin "P$43") (pinfunction "GND2_P$43") (pintype "bidirectional"))
      (node (ref "CONN3") (pin "P$41") (pinfunction "GND1_P$41") (pintype "bidirectional"))
      (node (ref "CONN3") (pin "P$43") (pinfunction "GND2_P$43") (pintype "bidirectional"))
      (node (ref "D1") (pin "P$4") (pinfunction "P$4_P$4") (pintype "bidirectional"))
      (node (ref "D2") (pin "A") (pinfunction "A_A") (pintype "passive"))
      (node (ref "J1") (pin "2") (pinfunction "S_2") (pintype "passive"))
      (node (ref "J1") (pin "3") (pinfunction "S_3") (pintype "passive"))
      (node (ref "JP2") (pin "5") (pinfunction "SLEEVE_5") (pintype "bidirectional"))
      (node (ref "L2") (pin "1") (pinfunction "1_1") (pintype "passive"))
      (node (ref "R13") (pin "E") (pinfunction "E_E") (pintype "passive"))
      (node (ref "R13") (pin "S") (pinfunction "S_S") (pintype "passive"))
      (node (ref "TP2") (pin "TP") (pinfunction "TP_TP") (pintype "input"))
      (node (ref "TP3") (pin "TP") (pinfunction "TP_TP") (pintype "input"))
      (node (ref "U1") (pin "1") (pinfunction "G1_1") (pintype "input"))
      (node (ref "U1") (pin "19") (pinfunction "G2_19") (pintype "input"))
      (node (ref "U12") (pin "3") (pinfunction "GND_3") (pintype "power_in"))
      (node (ref "U12") (pin "5") (pinfunction "~{ON}/OFF_5") (pintype "input"))
      (node (ref "U2") (pin "1") (pinfunction "GAB_1") (pintype "input"))
      (node (ref "U2") (pin "13") (pinfunction "GBA_13") (pintype "input"))
      (node (ref "U2") (pin "6") (pinfunction "A4_6") (pintype "bidirectional"))
      (node (ref "U4") (pin "1") (pinfunction "G1_1") (pintype "input"))
      (node (ref "U4") (pin "19") (pinfunction "G2_19") (pintype "input"))
      (node (ref "U5") (pin "1") (pinfunction "G1_1") (pintype "input"))
      (node (ref "U5") (pin "19") (pinfunction "G2_19") (pintype "input"))
      (node (ref "U7") (pin "19") (pinfunction "G_19") (pintype "input"))
      (node (ref "U8") (pin "1") (pinfunction "OC_1") (pintype "input"))
    )
    (net (code "89") (name "Net-(C13-Pad+)") (class "Default")
      (node (ref "C13") (pin "+") (pinfunction "+_+") (pintype "passive"))
      (node (ref "R1") (pin "2") (pinfunction "2_2") (pintype "passive"))
      (node (ref "R15") (pin "2") (pinfunction "2_2") (pintype "passive"))
      (node (ref "R16") (pin "2") (pinfunction "2_2") (pintype "passive"))
      (node (ref "R2") (pin "2") (pinfunction "2_2") (pintype "passive"))
    )
    (net (code "90") (name "Net-(C14-Pad-)") (class "Default")
      (node (ref "C14") (pin "-") (pinfunction "-_-") (pintype "passive"))
      (node (ref "C15") (pin "2") (pinfunction "2_2") (pintype "passive"))
      (node (ref "D3") (pin "A") (pinfunction "A_A") (pintype "passive"))
      (node (ref "L3") (pin "2") (pinfunction "2_2") (pintype "passive"))
      (node (ref "R14") (pin "2") (pinfunction "2_2") (pintype "passive"))
      (node (ref "U11") (pin "4") (pinfunction "4_4") (pintype "passive"))
    )
    (net (code "91") (name "Net-(C15-Pad1)") (class "Default")
      (node (ref "C15") (pin "1") (pinfunction "1_1") (pintype "passive"))
      (node (ref "U11") (pin "3") (pinfunction "3_3") (pintype "passive"))
    )
    (net (code "92") (name "Net-(CONN2-SNDIN)") (class "Default")
      (node (ref "CONN2") (pin "P$49") (pinfunction "SNDIN_P$49") (pintype "bidirectional"))
      (node (ref "R1") (pin "1") (pinfunction "1_1") (pintype "passive"))
    )
    (net (code "93") (name "Net-(CONN3-SNDIN)") (class "Default")
      (node (ref "CONN3") (pin "P$49") (pinfunction "SNDIN_P$49") (pintype "bidirectional"))
      (node (ref "R2") (pin "1") (pinfunction "1_1") (pintype "passive"))
    )
    (net (code "94") (name "Net-(D1-PadP$1)") (class "Default")
      (node (ref "D1") (pin "P$1") (pinfunction "P$1_P$1") (pintype "bidirectional"))
      (node (ref "JP1") (pin "PWR") (pinfunction "PWR_PWR") (pintype "bidirectional"))
    )
    (net (code "95") (name "Net-(D1-PadP$3)") (class "Default")
      (node (ref "D1") (pin "P$3") (pinfunction "P$3_P$3") (pintype "bidirectional"))
      (node (ref "JP1") (pin "GND") (pinfunction "GND_GND") (pintype "bidirectional"))
      (node (ref "JP1") (pin "GNDBREAK") (pinfunction "GNDBREAK_GNDBREAK") (pintype "bidirectional"))
    )
    (net (code "96") (name "Net-(D3-PadC)") (class "Default")
      (node (ref "D3") (pin "C") (pinfunction "C_C") (pintype "passive"))
      (node (ref "L2") (pin "2") (pinfunction "2_2") (pintype "passive"))
      (node (ref "U11") (pin "2") (pinfunction "2_2") (pintype "passive"))
    )
    (net (code "97") (name "Net-(JP2-LEFT)") (class "Default")
      (node (ref "JP2") (pin "1") (pinfunction "LEFT_1") (pintype "bidirectional"))
      (node (ref "R16") (pin "1") (pinfunction "1_1") (pintype "passive"))
    )
    (net (code "98") (name "Net-(JP2-RIGHT)") (class "Default")
      (node (ref "JP2") (pin "4") (pinfunction "RIGHT_4") (pintype "bidirectional"))
      (node (ref "R15") (pin "1") (pinfunction "1_1") (pintype "passive"))
    )
    (net (code "99") (name "Net-(R12-Pad2)") (class "Default")
      (node (ref "R12") (pin "2") (pinfunction "2_2") (pintype "passive"))
      (node (ref "U11") (pin "1") (pinfunction "1_1") (pintype "passive"))
      (node (ref "U11") (pin "7") (pinfunction "7_7") (pintype "passive"))
      (node (ref "U11") (pin "8") (pinfunction "8_8") (pintype "passive"))
    )
    (net (code "100") (name "Net-(R13-PadA)") (class "Default")
      (node (ref "R13") (pin "A") (pinfunction "A_A") (pintype "passive"))
      (node (ref "R14") (pin "1") (pinfunction "1_1") (pintype "passive"))
      (node (ref "U11") (pin "5") (pinfunction "5_5") (pintype "passive"))
    )
    (net (code "101") (name "Net-(S1-O)") (class "Default")
      (node (ref "D1") (pin "P$2") (pinfunction "P$2_P$2") (pintype "bidirectional"))
      (node (ref "S1") (pin "1") (pinfunction "O_1") (pintype "passive"))
    )
    (net (code "102") (name "Net-(U8A-1Q)") (class "Default")
      (node (ref "U8") (pin "19") (pinfunction "1Q_19") (pintype "tri_state"))
      (node (ref "U9") (pin "6") (pinfunction "1C0_6") (pintype "input"))
    )
    (net (code "103") (name "Net-(U8A-2Q)") (class "Default")
      (node (ref "U8") (pin "18") (pinfunction "2Q_18") (pintype "tri_state"))
      (node (ref "U9") (pin "10") (pinfunction "2C0_10") (pintype "input"))
    )
    (net (code "104") (name "Net-(U8A-3Q)") (class "Default")
      (node (ref "U8") (pin "17") (pinfunction "3Q_17") (pintype "tri_state"))
      (node (ref "U9") (pin "5") (pinfunction "1C1_5") (pintype "input"))
    )
    (net (code "105") (name "Net-(U8A-4Q)") (class "Default")
      (node (ref "U8") (pin "16") (pinfunction "4Q_16") (pintype "tri_state"))
      (node (ref "U9") (pin "11") (pinfunction "2C1_11") (pintype "input"))
    )
    (net (code "106") (name "Net-(U8A-5Q)") (class "Default")
      (node (ref "U8") (pin "15") (pinfunction "5Q_15") (pintype "tri_state"))
      (node (ref "U9") (pin "4") (pinfunction "1C2_4") (pintype "input"))
    )
    (net (code "107") (name "Net-(U8A-6Q)") (class "Default")
      (node (ref "U8") (pin "14") (pinfunction "6Q_14") (pintype "tri_state"))
      (node (ref "U9") (pin "12") (pinfunction "2C2_12") (pintype "input"))
    )
    (net (code "108") (name "Net-(U8A-7Q)") (class "Default")
      (node (ref "U8") (pin "13") (pinfunction "7Q_13") (pintype "tri_state"))
      (node (ref "U9") (pin "3") (pinfunction "1C3_3") (pintype "input"))
    )
    (net (code "109") (name "Net-(U8A-8Q)") (class "Default")
      (node (ref "U8") (pin "12") (pinfunction "8Q_12") (pintype "tri_state"))
      (node (ref "U9") (pin "13") (pinfunction "2C3_13") (pintype "input"))
    )
    (net (code "110") (name "Net-(U10A-I1)") (class "Default")
      (node (ref "U10") (pin "2") (pinfunction "I1_2") (pintype "input"))
      (node (ref "U10") (pin "6") (pinfunction "O_6") (pintype "output"))
    )
    (net (code "111") (name "Net-(U10A-O)") (class "Default")
      (node (ref "U10") (pin "3") (pinfunction "O_3") (pintype "output"))
      (node (ref "U10") (pin "4") (pinfunction "I0_4") (pintype "input"))
      (node (ref "U9") (pin "1") (pinfunction "1G_1") (pintype "input"))
      (node (ref "U9") (pin "15") (pinfunction "2G_15") (pintype "input"))
    )
    (net (code "112") (name "Net-(U10C-O)") (class "Default")
      (node (ref "U10") (pin "12") (pinfunction "I0_12") (pintype "input"))
      (node (ref "U10") (pin "13") (pinfunction "I1_13") (pintype "input"))
      (node (ref "U10") (pin "8") (pinfunction "O_8") (pintype "output"))
    )
    (net (code "113") (name "Net-(U12-OUT)") (class "Default")
      (node (ref "D2") (pin "C") (pinfunction "C_C") (pintype "passive"))
      (node (ref "L1") (pin "1") (pinfunction "1_1") (pintype "passive"))
      (node (ref "U12") (pin "2") (pinfunction "OUT_2") (pintype "output"))
    )
    (net (code "114") (name "SLOTA") (class "Default")
      (node (ref "U6") (pin "19") (pinfunction "O5_19") (pintype "bidirectional"))
      (node (ref "U9") (pin "7") (pinfunction "1Y_7") (pintype "output"))
    )
    (net (code "115") (name "SLOTB") (class "Default")
      (node (ref "U6") (pin "18") (pinfunction "O4_18") (pintype "bidirectional"))
      (node (ref "U9") (pin "9") (pinfunction "2Y_9") (pintype "output"))
    )
    (net (code "116") (name "SNDIN") (class "Default")
      (node (ref "C13") (pin "-") (pinfunction "-_-") (pintype "passive"))
    )
    (net (code "117") (name "SW1_2") (class "Default")
      (node (ref "CONN2") (pin "P$44") (pinfunction "SW1_P$44") (pintype "bidirectional"))
    )
    (net (code "118") (name "SW1_3") (class "Default")
      (node (ref "CONN3") (pin "P$44") (pinfunction "SW1_P$44") (pintype "bidirectional"))
    )
    (net (code "119") (name "SW2_2") (class "Default")
      (node (ref "CONN2") (pin "P$46") (pinfunction "SW2_P$46") (pintype "bidirectional"))
    )
    (net (code "120") (name "SW2_3") (class "Default")
      (node (ref "CONN3") (pin "P$46") (pinfunction "SW2_P$46") (pintype "bidirectional"))
    )
    (net (code "121") (name "VCC") (class "Default")
      (node (ref "C10") (pin "1") (pinfunction "1_1") (pintype "passive"))
      (node (ref "C11") (pin "1") (pinfunction "1_1") (pintype "passive"))
      (node (ref "C12") (pin "1") (pinfunction "1_1") (pintype "passive"))
      (node (ref "C17") (pin "1") (pinfunction "1_1") (pintype "passive"))
      (node (ref "C2") (pin "+") (pinfunction "+_+") (pintype "passive"))
      (node (ref "C3") (pin "1") (pinfunction "1_1") (pintype "passive"))
      (node (ref "C4") (pin "1") (pinfunction "1_1") (pintype "passive"))
      (node (ref "C5") (pin "1") (pinfunction "1_1") (pintype "passive"))
      (node (ref "C6") (pin "1") (pinfunction "1_1") (pintype "passive"))
      (node (ref "C7") (pin "1") (pinfunction "1_1") (pintype "passive"))
      (node (ref "C8") (pin "1") (pinfunction "1_1") (pintype "passive"))
      (node (ref "C9") (pin "1") (pinfunction "1_1") (pintype "passive"))
      (node (ref "CONN2") (pin "P$45") (pinfunction "+5V1_P$45") (pintype "bidirectional"))
      (node (ref "CONN2") (pin "P$47") (pinfunction "+5V2_P$47") (pintype "bidirectional"))
      (node (ref "CONN3") (pin "P$45") (pinfunction "+5V1_P$45") (pintype "bidirectional"))
      (node (ref "CONN3") (pin "P$47") (pinfunction "+5V2_P$47") (pintype "bidirectional"))
      (node (ref "J1") (pin "1") (pinfunction "S_1") (pintype "passive"))
      (node (ref "L1") (pin "2") (pinfunction "2_2") (pintype "passive"))
      (node (ref "R10") (pin "2") (pinfunction "2_2") (pintype "passive"))
      (node (ref "R11") (pin "2") (pinfunction "2_2") (pintype "passive"))
      (node (ref "R12") (pin "1") (pinfunction "1_1") (pintype "passive"))
      (node (ref "R3") (pin "1") (pinfunction "1_1") (pintype "passive"))
      (node (ref "R4") (pin "1") (pinfunction "1_1") (pintype "passive"))
      (node (ref "R5") (pin "1") (pinfunction "1_1") (pintype "passive"))
      (node (ref "R6") (pin "2") (pinfunction "2_2") (pintype "passive"))
      (node (ref "R7") (pin "2") (pinfunction "2_2") (pintype "passive"))
      (node (ref "R8") (pin "2") (pinfunction "2_2") (pintype "passive"))
      (node (ref "R9") (pin "2") (pinfunction "2_2") (pintype "passive"))
      (node (ref "TP4") (pin "TP") (pinfunction "TP_TP") (pintype "input"))
      (node (ref "U11") (pin "6") (pinfunction "6_6") (pintype "passive"))
      (node (ref "U12") (pin "4") (pinfunction "FB_4") (pintype "input"))
    )
    (net (code "122") (name "unconnected-(CONN2-NC1-PadP$5)") (class "Default")
      (node (ref "CONN2") (pin "P$5") (pinfunction "NC1_P$5") (pintype "bidirectional"))
    )
    (net (code "123") (name "unconnected-(CONN2-NC2-PadP$16)") (class "Default")
      (node (ref "CONN2") (pin "P$16") (pinfunction "NC2_P$16") (pintype "bidirectional"))
    )
    (net (code "124") (name "unconnected-(CONN3-NC1-PadP$5)") (class "Default")
      (node (ref "CONN3") (pin "P$5") (pinfunction "NC1_P$5") (pintype "bidirectional"))
    )
    (net (code "125") (name "unconnected-(CONN3-NC2-PadP$16)") (class "Default")
      (node (ref "CONN3") (pin "P$16") (pinfunction "NC2_P$16") (pintype "bidirectional"))
    )
    (net (code "126") (name "unconnected-(S1-PadB)") (class "Default")
      (node (ref "S1") (pin "B") (pinfunction "B_B") (pintype "passive"))
    )
    (net (code "127") (name "unconnected-(S1-PadB1)") (class "Default")
      (node (ref "S1") (pin "B1") (pinfunction "B1_B1") (pintype "passive"))
    )
    (net (code "128") (name "unconnected-(S1-S-Pad3)") (class "Default")
      (node (ref "S1") (pin "3") (pinfunction "S_3") (pintype "passive"))
    )
    (net (code "129") (name "unconnected-(U2A-B4-Pad8)") (class "Default")
      (node (ref "U2") (pin "8") (pinfunction "B4_8") (pintype "bidirectional"))
    )
    (net (code "130") (name "unconnected-(U6A-O3-Pad17)") (class "Default")
      (node (ref "U6") (pin "17") (pinfunction "O3_17") (pintype "bidirectional"))
    )
  )
)
